# USB-PD.net
KiCad netlist of a schematic drawn in Altium Designer
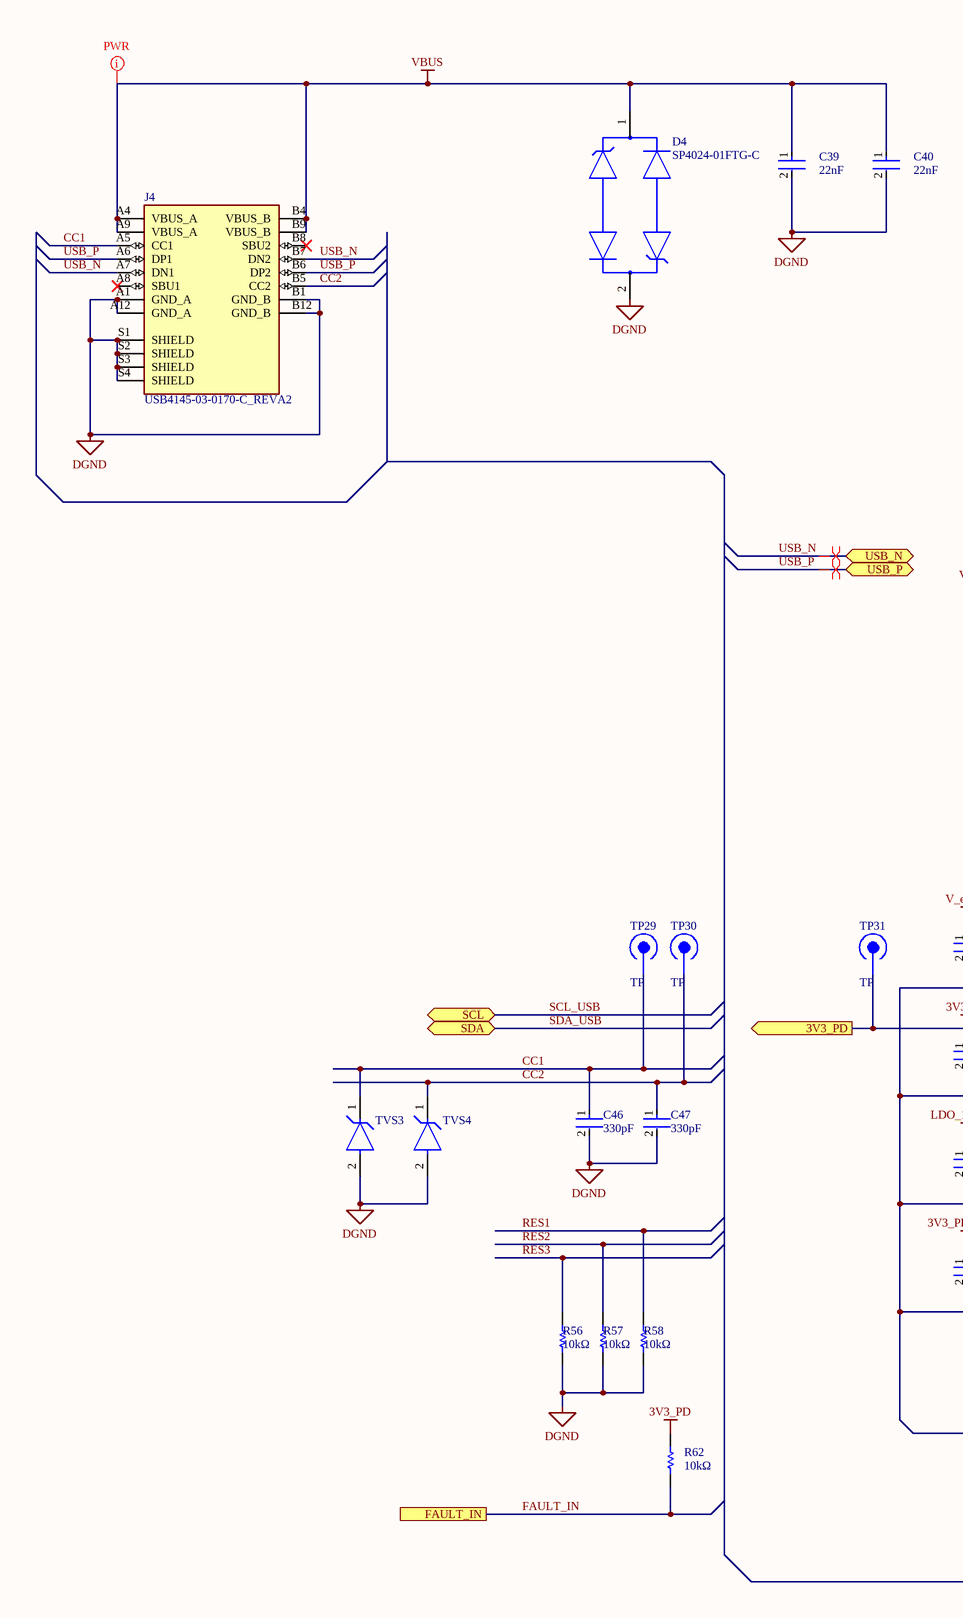
[diagram p0: USB-PD.SchDoc, left]
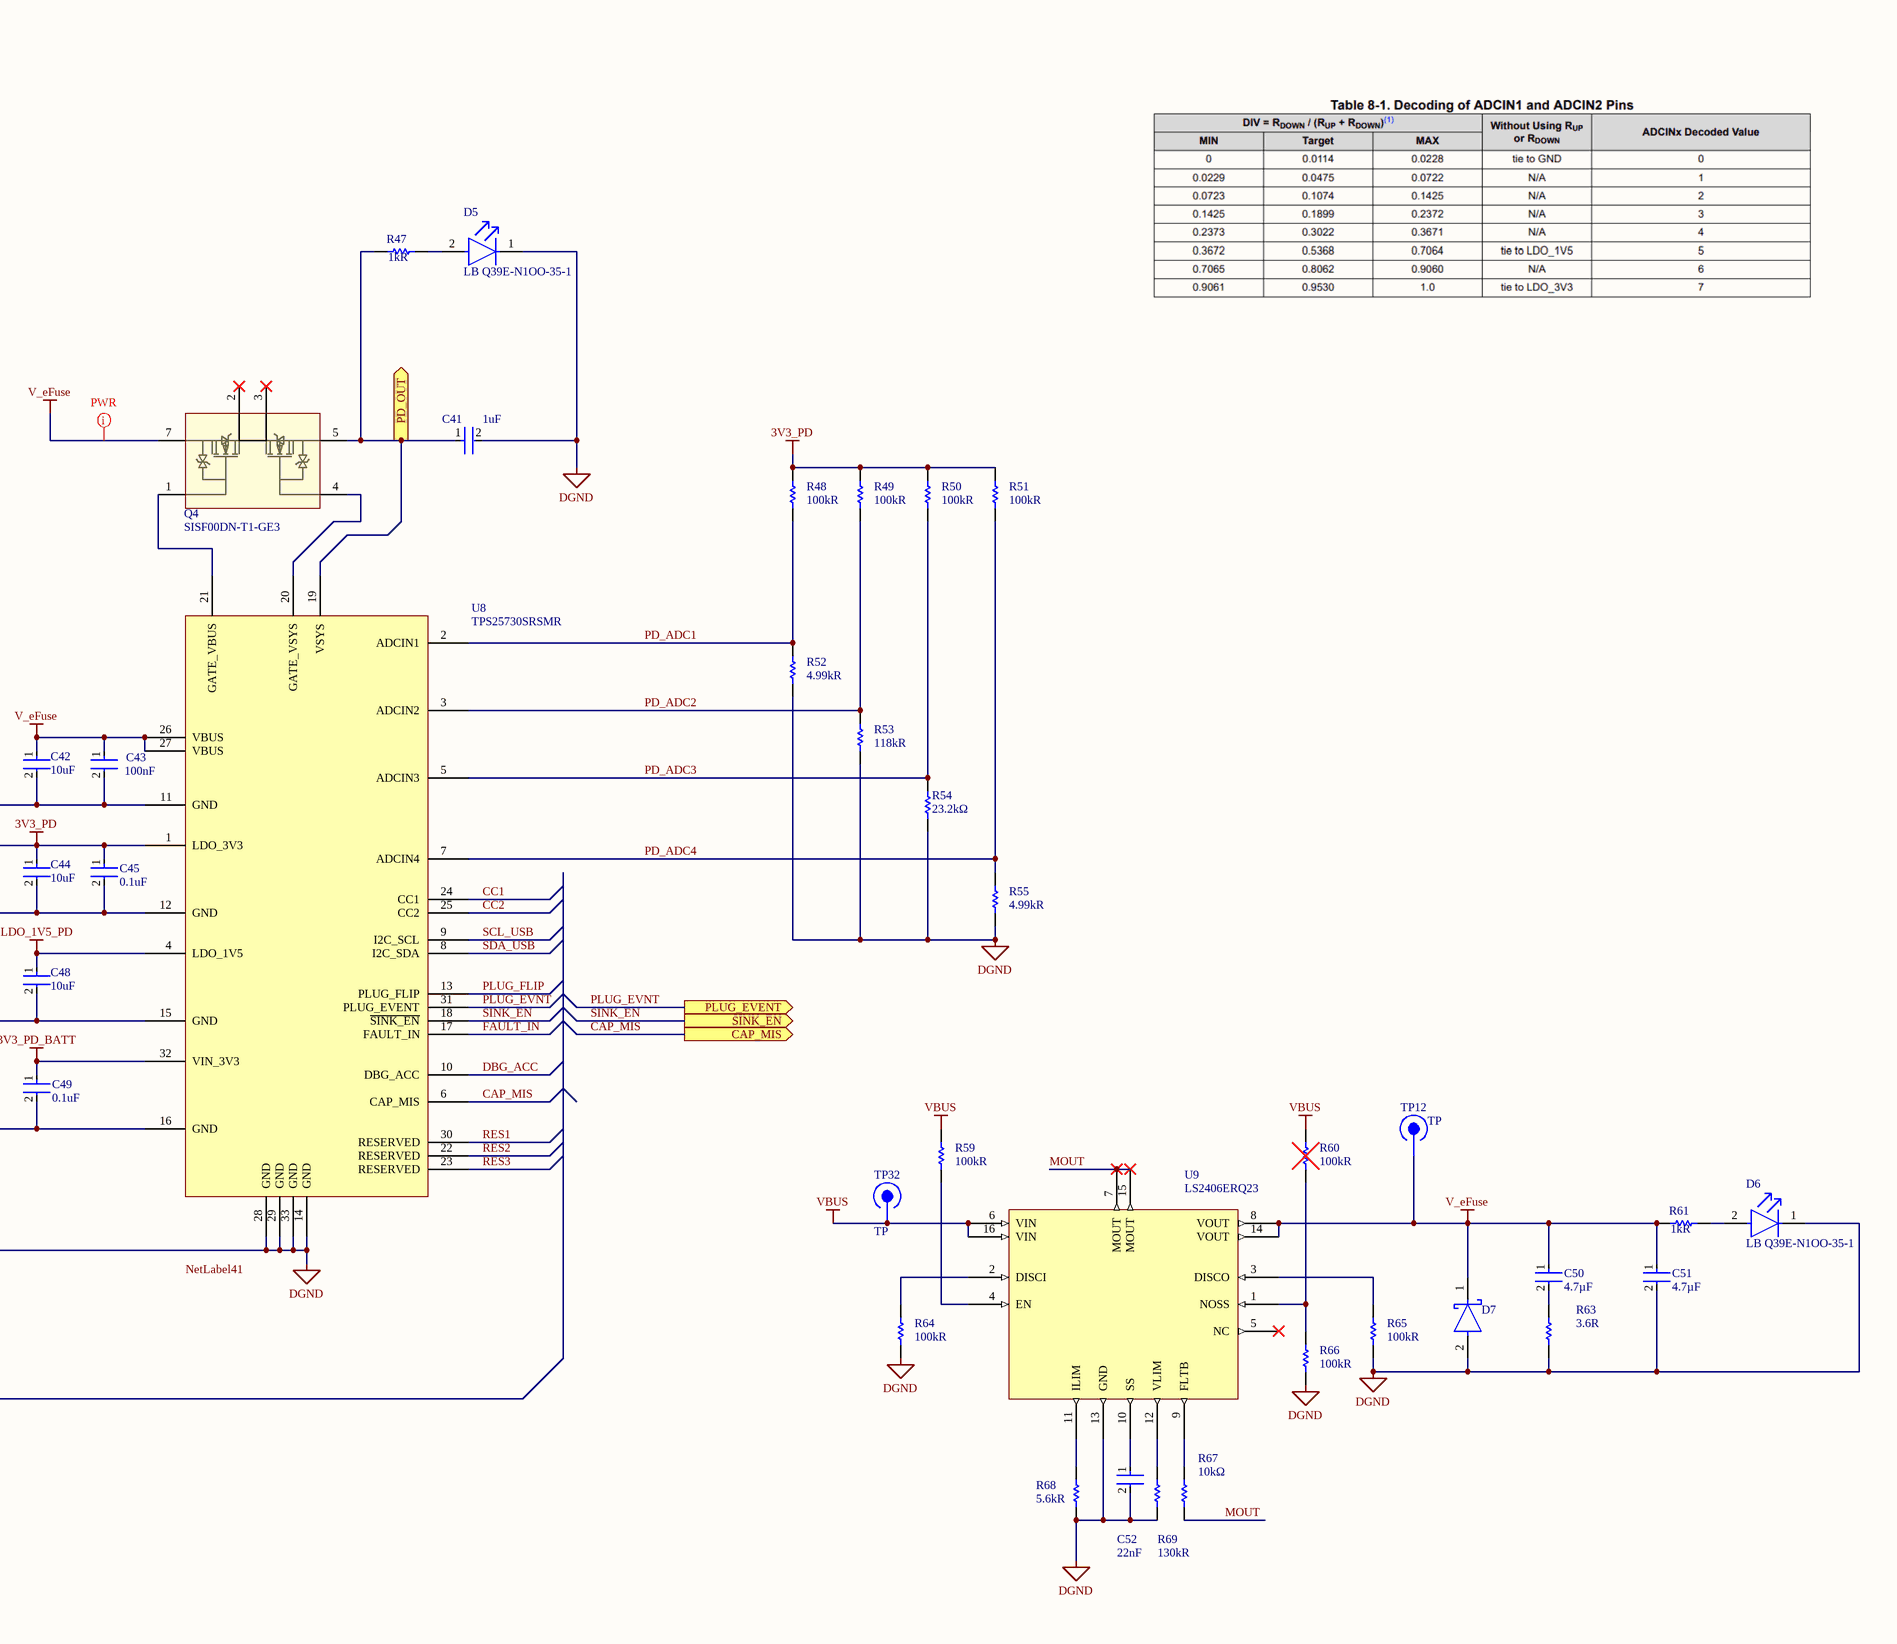
[diagram p1: USB-PD.SchDoc, right]

(export (version "E")
  (design (tool "Eeschema 10.0.6"))
  (components
    (comp (ref "C39")
      (value "22nF")
      (footprint "FP-GRM155-0_05-MFG")
      (fields (field (name "MANUFACTURER") "Murata") (field (name "Comment") "GRM155R71H223KA12D"))
      (libsource (lib "Digital Shovel") (part "02cd4be3c70576c341d710602a673aa"))
    )
    (comp (ref "C40")
      (value "22nF")
      (footprint "FP-GRM155-0_05-MFG")
      (fields (field (name "MANUFACTURER") "Murata") (field (name "Comment") "GRM155R71H223KA12D"))
      (libsource (lib "Digital Shovel") (part "02cd4be3c70576c341d710602a673aa"))
    )
    (comp (ref "C41")
      (value "1uF")
      (footprint "FP-GCM188-0_1-IPC_B")
      (fields (field (name "MANUFACTURER") "Murata") (field (name "Comment") "GCM188R71E105KA64J"))
      (libsource (lib "Digital Shovel") (part "02cd4be3c70576c341d710602a673aa"))
    )
    (comp (ref "C42")
      (value "10uF")
      (footprint "FP-GRM155-0_2-MFG")
      (fields (field (name "Comment") "GRM155R61A106ME11D"))
      (libsource (lib "Digital Shovel") (part "b4654b650e69147ec39a6b967a45e02"))
    )
    (comp (ref "C43")
      (value "100nF")
      (footprint "FP-CC0402-IPC_B")
      (fields (field (name "Comment") "CC0402KRX7R9BB104"))
      (libsource (lib "Digital Shovel") (part "11868f565c42a9108669ba33697ecf6"))
    )
    (comp (ref "C44")
      (value "10uF")
      (footprint "FP-GRM155-0_2-MFG")
      (fields (field (name "Comment") "GRM155R61A106ME11D"))
      (libsource (lib "Digital Shovel") (part "b4654b650e69147ec39a6b967a45e02"))
    )
    (comp (ref "C45")
      (value "0.1uF")
      (footprint "FP-CC0402-IPC_C")
      (description "Multilayer Ceramic Capacitor, 0.1 uF, 25 V, ± 10%, X7R, 0402 [1005 Metric]")
      (fields (field (name "Comment") "CC0402KRX7R7BB104"))
      (libsource (lib "Digital Shovel") (part "11868f565c42a9108669ba33697ecf6"))
    )
    (comp (ref "C46")
      (value "330pF")
      (footprint "FP-C0402-BB-MFG")
      (fields (field (name "MANUFACTURER") "Kemet") (field (name "Comment") "C0402C331K5RACTU"))
      (libsource (lib "Digital Shovel") (part "b4654b650e69147ec39a6b967a45e02"))
    )
    (comp (ref "C47")
      (value "330pF")
      (footprint "FP-C0402-BB-MFG")
      (fields (field (name "MANUFACTURER") "Kemet") (field (name "Comment") "C0402C331K5RACTU"))
      (libsource (lib "Digital Shovel") (part "b4654b650e69147ec39a6b967a45e02"))
    )
    (comp (ref "C48")
      (value "10uF")
      (footprint "FP-GRM155-0_2-MFG")
      (fields (field (name "Comment") "GRM155R61A106ME11D"))
      (libsource (lib "Digital Shovel") (part "b4654b650e69147ec39a6b967a45e02"))
    )
    (comp (ref "C49")
      (value "0.1uF")
      (footprint "FP-CC0402-IPC_C")
      (description "Multilayer Ceramic Capacitor, 0.1 uF, 25 V, ± 10%, X7R, 0402 [1005 Metric]")
      (fields (field (name "Comment") "CC0402KRX7R7BB104"))
      (libsource (lib "Digital Shovel") (part "11868f565c42a9108669ba33697ecf6"))
    )
    (comp (ref "C50")
      (value "4.7µF")
      (footprint "FP-GRM21B-0_15-IPC_A")
      (fields (field (name "Comment") "GRM21BR61H475KE51L"))
      (libsource (lib "Digital Shovel") (part "b4654b650e69147ec39a6b967a45e02"))
    )
    (comp (ref "C51")
      (value "4.7µF")
      (footprint "FP-GRM21B-0_15-IPC_A")
      (fields (field (name "Comment") "GRM21BR61H475KE51L"))
      (libsource (lib "Digital Shovel") (part "b4654b650e69147ec39a6b967a45e02"))
    )
    (comp (ref "C52")
      (value "22nF")
      (footprint "FP-GRM155-0_05-MFG")
      (fields (field (name "MANUFACTURER") "Murata") (field (name "Comment") "GRM155R71H223KA12D"))
      (libsource (lib "Digital Shovel") (part "02cd4be3c70576c341d710602a673aa"))
    )
    (comp (ref "D4")
      (value "SP4024-01FTG-C")
      (footprint "FP-SP4024-CA-MFG")
      (description "Trans Voltage Suppressor Diode, 350W, 24V V(RWM), Bidirectional, 1 Element, Silicon")
      (fields (field (name "MANUFACTURER") "Littelfuse"))
      (libsource (lib "Digital Shovel") (part "83d03e45b50b4a497300f60ade81f7d"))
    )
    (comp (ref "D5")
      (value "LB Q39E-N1OO-35-1")
      (footprint "FP-LB_Q39E-MFG")
      (description "LED BLUE DIFFUSED 0603 SMD")
      (libsource (lib "Altium Content Vault") (part "8706943c75ba83719d021d2fdc84c58"))
    )
    (comp (ref "D6")
      (value "LB Q39E-N1OO-35-1")
      (footprint "FP-LB_Q39E-MFG")
      (description "LED BLUE DIFFUSED 0603 SMD")
      (libsource (lib "Altium Content Vault") (part "8706943c75ba83719d021d2fdc84c58"))
    )
    (comp (ref "D7")
      (value "PMEG4030ER,115")
      (footprint "FP-SOD123W-MFG")
      (description "Rectifier Diode, Schottky, 1 Phase, 1 Element, 3A, 40V V(RRM), Silicon")
      (fields (field (name "MANUFACTURER") "Nexperia"))
      (libsource (lib "Digital Shovel") (part "e9b750318ede8d9850c058872da20e7"))
    )
    (comp (ref "J4")
      (value "USB4145-03-0170-C_REVA2")
      (footprint "GCT_USB4145-03-0170-C_REVA2")
      (libsource (lib "Digital Shovel") (part "USB4145-03-0170-C_REVA2"))
    )
    (comp (ref "Q4")
      (value "SISF00DN-T1-GE3")
      (footprint "New footprint 1")
      (description "Power Field-Effect Transistor")
      (fields (field (name "MANUFACTURER") "Vishay"))
      (libsource (lib "Digital Shovel") (part "New symbol 1"))
    )
    (comp (ref "R47")
      (value "1kR")
      (footprint "FP-ERA2A-MFG")
      (description "Fixed Resistor, Thin Film, 0.063W, 1000ohm, 50V, 0.1% +/-Tol, 25ppm/Cel, Surface Mount, 0402")
      (fields (field (name "MANUFACTURER") "Panasonic") (field (name "Comment") "ERA-2AEB102X"))
      (libsource (lib "Digital Shovel") (part "1029c3af85768c4190bb7ad29bc67b5"))
    )
    (comp (ref "R48")
      (value "100kR")
      (footprint "RESC1005X40X25LL10T10")
      (fields (field (name "Comment") "RK73H1ETTP1003F"))
      (libsource (lib "Digital Shovel") (part "RES"))
    )
    (comp (ref "R49")
      (value "100kR")
      (footprint "RESC1005X40X25LL10T10")
      (fields (field (name "Comment") "RK73H1ETTP1003F"))
      (libsource (lib "Digital Shovel") (part "RES"))
    )
    (comp (ref "R50")
      (value "100kR")
      (footprint "RESC1005X40X25LL10T10")
      (fields (field (name "Comment") "RK73H1ETTP1003F"))
      (libsource (lib "Digital Shovel") (part "RES"))
    )
    (comp (ref "R51")
      (value "100kR")
      (footprint "RESC1005X40X25LL10T10")
      (fields (field (name "Comment") "RK73H1ETTP1003F"))
      (libsource (lib "Digital Shovel") (part "RES"))
    )
    (comp (ref "R52")
      (value "4.99kR")
      (footprint "RESC1005X40X25LL10T10")
      (fields (field (name "Comment") "RK73H1ETTP4991F"))
      (libsource (lib "Digital Shovel") (part "RES"))
    )
    (comp (ref "R53")
      (value "118kR")
      (footprint "RESC1005X40X25LL10T10")
      (fields (field (name "Comment") "RK73H1ETTP1183F"))
      (libsource (lib "Digital Shovel") (part "RES"))
    )
    (comp (ref "R54")
      (value "23.2kΩ")
      (footprint "RESC1005X40X25LL10T10")
      (fields (field (name "Comment") "RK73H1ETTP2322F"))
      (libsource (lib "Digital Shovel") (part "RES"))
    )
    (comp (ref "R55")
      (value "4.99kR")
      (footprint "RESC1005X40X25LL10T10")
      (fields (field (name "Comment") "RK73H1ETTP4991F"))
      (libsource (lib "Digital Shovel") (part "RES"))
    )
    (comp (ref "R56")
      (value "10kΩ")
      (footprint "RESC1005X40X25LL10T10")
      (fields (field (name "Comment") "RK73B1ETTP103J"))
      (libsource (lib "Digital Shovel") (part "RES"))
    )
    (comp (ref "R57")
      (value "10kΩ")
      (footprint "RESC1005X40X25LL10T10")
      (fields (field (name "Comment") "RK73B1ETTP103J"))
      (libsource (lib "Digital Shovel") (part "RES"))
    )
    (comp (ref "R58")
      (value "10kΩ")
      (footprint "RESC1005X40X25LL10T10")
      (fields (field (name "Comment") "RK73B1ETTP103J"))
      (libsource (lib "Digital Shovel") (part "RES"))
    )
    (comp (ref "R59")
      (value "100kR")
      (footprint "RESC1005X40X25LL10T10")
      (fields (field (name "Comment") "RK73H1ETTP1003F"))
      (libsource (lib "Digital Shovel") (part "RES"))
    )
    (comp (ref "R60")
      (value "100kR")
      (footprint "RESC1005X40X25LL10T10")
      (fields (field (name "Comment") "RK73H1ETTP1003F"))
      (libsource (lib "Digital Shovel") (part "RES"))
    )
    (comp (ref "R61")
      (value "1kR")
      (footprint "FP-ERA2A-MFG")
      (description "Fixed Resistor, Thin Film, 0.063W, 1000ohm, 50V, 0.1% +/-Tol, 25ppm/Cel, Surface Mount, 0402")
      (fields (field (name "MANUFACTURER") "Panasonic") (field (name "Comment") "ERA-2AEB102X"))
      (libsource (lib "Digital Shovel") (part "1029c3af85768c4190bb7ad29bc67b5"))
    )
    (comp (ref "R62")
      (value "10kΩ")
      (footprint "RESC1005X40X25LL10T10")
      (fields (field (name "Comment") "RK73B1ETTP103J"))
      (libsource (lib "Digital Shovel") (part "RES"))
    )
    (comp (ref "R63")
      (value "3.6R")
      (footprint "FP-RK73H2A-MFG")
      (fields (field (name "Comment") "RK73H2ATTD3R60F"))
      (libsource (lib "Digital Shovel") (part "1029c3af85768c4190bb7ad29bc67b5"))
    )
    (comp (ref "R64")
      (value "100kR")
      (footprint "RESC1005X40X25LL10T10")
      (fields (field (name "Comment") "RK73H1ETTP1003F"))
      (libsource (lib "Digital Shovel") (part "RES"))
    )
    (comp (ref "R65")
      (value "100kR")
      (footprint "RESC1005X40X25LL10T10")
      (fields (field (name "Comment") "RK73H1ETTP1003F"))
      (libsource (lib "Digital Shovel") (part "RES"))
    )
    (comp (ref "R66")
      (value "100kR")
      (footprint "RESC1005X40X25LL10T10")
      (fields (field (name "Comment") "RK73H1ETTP1003F"))
      (libsource (lib "Digital Shovel") (part "RES"))
    )
    (comp (ref "R67")
      (value "10kΩ")
      (footprint "RESC1005X40X25LL10T10")
      (fields (field (name "Comment") "RK73B1ETTP103J"))
      (libsource (lib "Digital Shovel") (part "RES"))
    )
    (comp (ref "R68")
      (value "5.6kR")
      (footprint "RESC1005X40X25LL10T10")
      (fields (field (name "Comment") "RK73H1ETTP5601F"))
      (libsource (lib "Digital Shovel") (part "RES"))
    )
    (comp (ref "R69")
      (value "130kR")
      (footprint "RESC1005X40X25NL10T10")
      (fields (field (name "PART NUMBER") "RK73H1ETTP1303F") (field (name "MANUFACTURER") "KOA Speer"))
      (libsource (lib "Altium Content Vault") (part "RES"))
    )
    (comp (ref "TP12")
      (value "TP")
      (footprint "TP-Footprint-1")
      (description "digital shovel test point")
      (libsource (lib "Digital Shovel") (part "TP-Symbol-1"))
    )
    (comp (ref "TP29")
      (value "TP")
      (footprint "TP-Footprint-1")
      (description "digital shovel test point")
      (libsource (lib "Digital Shovel") (part "TP-Symbol-1"))
    )
    (comp (ref "TP30")
      (value "TP")
      (footprint "TP-Footprint-1")
      (description "digital shovel test point")
      (libsource (lib "Digital Shovel") (part "TP-Symbol-1"))
    )
    (comp (ref "TP31")
      (value "TP")
      (footprint "TP-Footprint-1")
      (description "digital shovel test point")
      (libsource (lib "Digital Shovel") (part "TP-Symbol-1"))
    )
    (comp (ref "TP32")
      (value "TP")
      (footprint "TP-Footprint-1")
      (description "digital shovel test point")
      (libsource (lib "Digital Shovel") (part "TP-Symbol-1"))
    )
    (comp (ref "TVS3")
      (value "PESD5Z5.0,115")
      (footprint "DIO_BAS716,115")
      (description "Trans Voltage Suppressor Diode, 180W, 5V V(RWM), Unidirectional, 1 Element, Silicon")
      (fields (field (name "MANUFACTURER") "Nexperia"))
      (libsource (lib "Digital Shovel") (part "PESD5Z5.0,115-Symbol-1"))
    )
    (comp (ref "TVS4")
      (value "PESD5Z5.0,115")
      (footprint "DIO_BAS716,115")
      (description "Trans Voltage Suppressor Diode, 180W, 5V V(RWM), Unidirectional, 1 Element, Silicon")
      (fields (field (name "MANUFACTURER") "Nexperia"))
      (libsource (lib "Digital Shovel") (part "PESD5Z5.0,115-Symbol-1"))
    )
    (comp (ref "U8")
      (value "TPS25730SRSMR")
      (footprint "QFN40P400X400X100_HS-33N")
      (fields (field (name "MANUFACTURER") "Texas Instruments"))
      (libsource (lib "Digital Shovel") (part "TPS25730SRSMR-Symbol-1"))
    )
    (comp (ref "U9")
      (value "LS2406ERQ23")
      (footprint "LS2406ERQ23-Footprint-1")
      (description "28V/6A Efuse With True Rcb & Frs")
      (fields (field (name "MANUFACTURER") "Littelfuse"))
      (libsource (lib "Digital Shovel") (part "LS2406ERQ23-Symbol-1"))
    )
  )
  (nets
    (net (code "1") (name "/CAP_MIS") (class "Default")
      (node (ref "U8") (pin "6") (pinfunction "CAP_MIS_6") (pintype "passive"))
    )
    (net (code "2") (name "/CC1") (class "Default")
      (node (ref "C46") (pin "1") (pinfunction "1_1") (pintype "passive"))
      (node (ref "J4") (pin "A5") (pinfunction "CC1_A5") (pintype "bidirectional"))
      (node (ref "TP29") (pin "1") (pintype "passive"))
      (node (ref "TVS3") (pin "1") (pinfunction "1_1") (pintype "passive"))
      (node (ref "U8") (pin "24") (pinfunction "CC1_24") (pintype "passive"))
    )
    (net (code "3") (name "/CC2") (class "Default")
      (node (ref "C47") (pin "1") (pinfunction "1_1") (pintype "passive"))
      (node (ref "J4") (pin "B5") (pinfunction "CC2_B5") (pintype "bidirectional"))
      (node (ref "TP30") (pin "1") (pintype "passive"))
      (node (ref "TVS4") (pin "1") (pinfunction "1_1") (pintype "passive"))
      (node (ref "U8") (pin "25") (pinfunction "CC2_25") (pintype "passive"))
    )
    (net (code "4") (name "/DBG_ACC") (class "Default")
      (node (ref "U8") (pin "10") (pinfunction "DBG_ACC_10") (pintype "passive"))
    )
    (net (code "5") (name "/FAULT_IN") (class "Default")
      (node (ref "R62") (pin "1") (pinfunction "1_1") (pintype "passive"))
      (node (ref "U8") (pin "17") (pinfunction "FAULT_IN_17") (pintype "passive"))
    )
    (net (code "6") (name "/MOUT") (class "Default")
      (node (ref "R67") (pin "1") (pinfunction "1_1") (pintype "passive"))
      (node (ref "U9") (pin "15") (pinfunction "MOUT_15") (pintype "output"))
      (node (ref "U9") (pin "7") (pinfunction "MOUT_7") (pintype "output"))
    )
    (net (code "8") (name "/PD_ADC1") (class "Default")
      (node (ref "R48") (pin "1") (pinfunction "1_1") (pintype "passive"))
      (node (ref "R52") (pin "2") (pinfunction "2_2") (pintype "passive"))
      (node (ref "U8") (pin "2") (pinfunction "ADCIN1_2") (pintype "passive"))
    )
    (net (code "9") (name "/PD_ADC2") (class "Default")
      (node (ref "R49") (pin "1") (pinfunction "1_1") (pintype "passive"))
      (node (ref "R53") (pin "2") (pinfunction "2_2") (pintype "passive"))
      (node (ref "U8") (pin "3") (pinfunction "ADCIN2_3") (pintype "passive"))
    )
    (net (code "10") (name "/PD_ADC3") (class "Default")
      (node (ref "R50") (pin "1") (pinfunction "1_1") (pintype "passive"))
      (node (ref "R54") (pin "2") (pinfunction "2_2") (pintype "passive"))
      (node (ref "U8") (pin "5") (pinfunction "ADCIN3_5") (pintype "passive"))
    )
    (net (code "11") (name "/PD_ADC4") (class "Default")
      (node (ref "R51") (pin "1") (pinfunction "1_1") (pintype "passive"))
      (node (ref "R55") (pin "2") (pinfunction "2_2") (pintype "passive"))
      (node (ref "U8") (pin "7") (pinfunction "ADCIN4_7") (pintype "passive"))
    )
    (net (code "12") (name "/PD_OUT") (class "Default")
      (node (ref "C41") (pin "1") (pinfunction "1_1") (pintype "passive"))
      (node (ref "Q4") (pin "5") (pinfunction "S2_5") (pintype "passive"))
      (node (ref "R47") (pin "2") (pinfunction "2_2") (pintype "passive"))
      (node (ref "U8") (pin "19") (pinfunction "VSYS_19") (pintype "passive"))
    )
    (net (code "13") (name "/PLUG_EVNT") (class "Default")
      (node (ref "U8") (pin "31") (pinfunction "PLUG_EVENT_31") (pintype "passive"))
    )
    (net (code "14") (name "/PLUG_FLIP") (class "Default")
      (node (ref "U8") (pin "13") (pinfunction "PLUG_FLIP_13") (pintype "passive"))
    )
    (net (code "15") (name "/RES1") (class "Default")
      (node (ref "R58") (pin "2") (pinfunction "2_2") (pintype "passive"))
      (node (ref "U8") (pin "30") (pinfunction "RESERVED_30") (pintype "passive"))
    )
    (net (code "16") (name "/RES2") (class "Default")
      (node (ref "R57") (pin "2") (pinfunction "2_2") (pintype "passive"))
      (node (ref "U8") (pin "22") (pinfunction "RESERVED_22") (pintype "passive"))
    )
    (net (code "17") (name "/RES3") (class "Default")
      (node (ref "R56") (pin "2") (pinfunction "2_2") (pintype "passive"))
      (node (ref "U8") (pin "23") (pinfunction "RESERVED_23") (pintype "passive"))
    )
    (net (code "18") (name "/SCL_USB") (class "Default")
      (node (ref "U8") (pin "9") (pinfunction "I2C_SCL_9") (pintype "passive"))
    )
    (net (code "19") (name "/SDA_USB") (class "Default")
      (node (ref "U8") (pin "8") (pinfunction "I2C_SDA_8") (pintype "passive"))
    )
    (net (code "20") (name "/SINK_EN") (class "Default")
      (node (ref "U8") (pin "18") (pinfunction "~{SINK_EN}_18") (pintype "passive"))
    )
    (net (code "21") (name "/USB_N") (class "Default")
      (node (ref "J4") (pin "A7") (pinfunction "DN1_A7") (pintype "bidirectional"))
      (node (ref "J4") (pin "B7") (pinfunction "DN2_B7") (pintype "bidirectional"))
    )
    (net (code "22") (name "/USB_P") (class "Default")
      (node (ref "J4") (pin "A6") (pinfunction "DP1_A6") (pintype "bidirectional"))
      (node (ref "J4") (pin "B6") (pinfunction "DP2_B6") (pintype "bidirectional"))
    )
    (net (code "23") (name "3V3_PD") (class "Default")
      (node (ref "C44") (pin "1") (pinfunction "1_1") (pintype "passive"))
      (node (ref "C45") (pin "1") (pinfunction "1_1") (pintype "passive"))
      (node (ref "R48") (pin "2") (pinfunction "2_2") (pintype "passive"))
      (node (ref "R49") (pin "2") (pinfunction "2_2") (pintype "passive"))
      (node (ref "R50") (pin "2") (pinfunction "2_2") (pintype "passive"))
      (node (ref "R51") (pin "2") (pinfunction "2_2") (pintype "passive"))
      (node (ref "R62") (pin "2") (pinfunction "2_2") (pintype "passive"))
      (node (ref "TP31") (pin "1") (pintype "passive"))
      (node (ref "U8") (pin "1") (pinfunction "LDO_3V3_1") (pintype "passive"))
    )
    (net (code "24") (name "3V3_PD_BATT") (class "Default")
      (node (ref "C49") (pin "1") (pinfunction "1_1") (pintype "passive"))
      (node (ref "U8") (pin "32") (pinfunction "VIN_3V3_32") (pintype "passive"))
    )
    (net (code "25") (name "DGND") (class "Default")
      (node (ref "C39") (pin "2") (pinfunction "2_2") (pintype "passive"))
      (node (ref "C40") (pin "2") (pinfunction "2_2") (pintype "passive"))
      (node (ref "C41") (pin "2") (pinfunction "2_2") (pintype "passive"))
      (node (ref "C42") (pin "2") (pinfunction "2_2") (pintype "passive"))
      (node (ref "C43") (pin "2") (pinfunction "2_2") (pintype "passive"))
      (node (ref "C44") (pin "2") (pinfunction "2_2") (pintype "passive"))
      (node (ref "C45") (pin "2") (pinfunction "2_2") (pintype "passive"))
      (node (ref "C46") (pin "2") (pinfunction "2_2") (pintype "passive"))
      (node (ref "C47") (pin "2") (pinfunction "2_2") (pintype "passive"))
      (node (ref "C48") (pin "2") (pinfunction "2_2") (pintype "passive"))
      (node (ref "C49") (pin "2") (pinfunction "2_2") (pintype "passive"))
      (node (ref "C51") (pin "2") (pinfunction "2_2") (pintype "passive"))
      (node (ref "C52") (pin "2") (pinfunction "2_2") (pintype "passive"))
      (node (ref "D4") (pin "2") (pinfunction "2_2") (pintype "passive"))
      (node (ref "D5") (pin "1") (pinfunction "C_1") (pintype "passive"))
      (node (ref "D6") (pin "1") (pinfunction "C_1") (pintype "passive"))
      (node (ref "D7") (pin "2") (pinfunction "A_2") (pintype "passive"))
      (node (ref "J4") (pin "A1") (pinfunction "GND_A_A1") (pintype "power_in"))
      (node (ref "J4") (pin "A12") (pinfunction "GND_A_A12") (pintype "power_in"))
      (node (ref "J4") (pin "B1") (pinfunction "GND_B_B1") (pintype "power_in"))
      (node (ref "J4") (pin "B12") (pinfunction "GND_B_B12") (pintype "power_in"))
      (node (ref "J4") (pin "S1") (pinfunction "SHIELD_S1") (pintype "passive"))
      (node (ref "J4") (pin "S2") (pinfunction "SHIELD_S2") (pintype "passive"))
      (node (ref "J4") (pin "S3") (pinfunction "SHIELD_S3") (pintype "passive"))
      (node (ref "J4") (pin "S4") (pinfunction "SHIELD_S4") (pintype "passive"))
      (node (ref "R52") (pin "1") (pinfunction "1_1") (pintype "passive"))
      (node (ref "R53") (pin "1") (pinfunction "1_1") (pintype "passive"))
      (node (ref "R54") (pin "1") (pinfunction "1_1") (pintype "passive"))
      (node (ref "R55") (pin "1") (pinfunction "1_1") (pintype "passive"))
      (node (ref "R56") (pin "1") (pinfunction "1_1") (pintype "passive"))
      (node (ref "R57") (pin "1") (pinfunction "1_1") (pintype "passive"))
      (node (ref "R58") (pin "1") (pinfunction "1_1") (pintype "passive"))
      (node (ref "R63") (pin "1") (pinfunction "1_1") (pintype "passive"))
      (node (ref "R64") (pin "1") (pinfunction "1_1") (pintype "passive"))
      (node (ref "R65") (pin "1") (pinfunction "1_1") (pintype "passive"))
      (node (ref "R66") (pin "1") (pinfunction "1_1") (pintype "passive"))
      (node (ref "R68") (pin "1") (pinfunction "1_1") (pintype "passive"))
      (node (ref "R69") (pin "1") (pinfunction "1_1") (pintype "passive"))
      (node (ref "TVS3") (pin "2") (pinfunction "1_2") (pintype "passive"))
      (node (ref "TVS4") (pin "2") (pinfunction "1_2") (pintype "passive"))
      (node (ref "U8") (pin "11") (pinfunction "GND_11") (pintype "passive"))
      (node (ref "U8") (pin "12") (pinfunction "GND_12") (pintype "passive"))
      (node (ref "U8") (pin "14") (pinfunction "GND_14") (pintype "passive"))
      (node (ref "U8") (pin "15") (pinfunction "GND_15") (pintype "passive"))
      (node (ref "U8") (pin "16") (pinfunction "GND_16") (pintype "passive"))
      (node (ref "U8") (pin "28") (pinfunction "GND_28") (pintype "passive"))
      (node (ref "U8") (pin "29") (pinfunction "GND_29") (pintype "passive"))
      (node (ref "U8") (pin "33") (pinfunction "GND_33") (pintype "passive"))
      (node (ref "U9") (pin "13") (pinfunction "GND_13") (pintype "output"))
    )
    (net (code "26") (name "LDO_1V5_PD") (class "Default")
      (node (ref "C48") (pin "1") (pinfunction "1_1") (pintype "passive"))
      (node (ref "U8") (pin "4") (pinfunction "LDO_1V5_4") (pintype "passive"))
    )
    (net (code "27") (name "Net-(C50-Pad2)") (class "Default")
      (node (ref "C50") (pin "2") (pinfunction "2_2") (pintype "passive"))
      (node (ref "R63") (pin "2") (pinfunction "2_2") (pintype "passive"))
    )
    (net (code "28") (name "Net-(D5-A)") (class "Default")
      (node (ref "D5") (pin "2") (pinfunction "A_2") (pintype "passive"))
      (node (ref "R47") (pin "1") (pinfunction "1_1") (pintype "passive"))
    )
    (net (code "29") (name "Net-(D6-A)") (class "Default")
      (node (ref "D6") (pin "2") (pinfunction "A_2") (pintype "passive"))
      (node (ref "R61") (pin "1") (pinfunction "1_1") (pintype "passive"))
    )
    (net (code "30") (name "Net-(Q4-G1)") (class "Default")
      (node (ref "Q4") (pin "1") (pinfunction "G1_1") (pintype "passive"))
      (node (ref "U8") (pin "21") (pinfunction "GATE_VBUS_21") (pintype "passive"))
    )
    (net (code "31") (name "Net-(Q4-G2)") (class "Default")
      (node (ref "Q4") (pin "4") (pinfunction "G2_4") (pintype "passive"))
      (node (ref "U8") (pin "20") (pinfunction "GATE_VSYS_20") (pintype "passive"))
    )
    (net (code "32") (name "Net-(U9-DISCI)") (class "Default")
      (node (ref "R64") (pin "2") (pinfunction "2_2") (pintype "passive"))
      (node (ref "U9") (pin "2") (pinfunction "DISCI_2") (pintype "input"))
    )
    (net (code "33") (name "Net-(U9-DISCO)") (class "Default")
      (node (ref "R65") (pin "2") (pinfunction "2_2") (pintype "passive"))
      (node (ref "U9") (pin "3") (pinfunction "DISCO_3") (pintype "input"))
    )
    (net (code "34") (name "Net-(U9-EN)") (class "Default")
      (node (ref "R59") (pin "1") (pinfunction "1_1") (pintype "passive"))
      (node (ref "U9") (pin "4") (pinfunction "EN_4") (pintype "input"))
    )
    (net (code "35") (name "Net-(U9-FLTB)") (class "Default")
      (node (ref "R67") (pin "2") (pinfunction "2_2") (pintype "passive"))
      (node (ref "U9") (pin "9") (pinfunction "FLTB_9") (pintype "output"))
    )
    (net (code "36") (name "Net-(U9-ILIM)") (class "Default")
      (node (ref "R68") (pin "2") (pinfunction "2_2") (pintype "passive"))
      (node (ref "U9") (pin "11") (pinfunction "ILIM_11") (pintype "output"))
    )
    (net (code "37") (name "Net-(U9-NOSS)") (class "Default")
      (node (ref "R60") (pin "1") (pinfunction "1_1") (pintype "passive"))
      (node (ref "R66") (pin "2") (pinfunction "2_2") (pintype "passive"))
      (node (ref "U9") (pin "1") (pinfunction "NOSS_1") (pintype "input"))
    )
    (net (code "38") (name "Net-(U9-SS)") (class "Default")
      (node (ref "C52") (pin "1") (pinfunction "1_1") (pintype "passive"))
      (node (ref "U9") (pin "10") (pinfunction "SS_10") (pintype "output"))
    )
    (net (code "39") (name "Net-(U9-VLIM)") (class "Default")
      (node (ref "R69") (pin "2") (pinfunction "2_2") (pintype "passive"))
      (node (ref "U9") (pin "12") (pinfunction "VLIM_12") (pintype "output"))
    )
    (net (code "40") (name "VBUS") (class "Default")
      (node (ref "C39") (pin "1") (pinfunction "1_1") (pintype "passive"))
      (node (ref "C40") (pin "1") (pinfunction "1_1") (pintype "passive"))
      (node (ref "D4") (pin "1") (pinfunction "1_1") (pintype "passive"))
      (node (ref "J4") (pin "A4") (pinfunction "VBUS_A_A4") (pintype "power_in"))
      (node (ref "J4") (pin "A9") (pinfunction "VBUS_A_A9") (pintype "power_in"))
      (node (ref "J4") (pin "B4") (pinfunction "VBUS_B_B4") (pintype "power_in"))
      (node (ref "J4") (pin "B9") (pinfunction "VBUS_B_B9") (pintype "power_in"))
      (node (ref "R59") (pin "2") (pinfunction "2_2") (pintype "passive"))
      (node (ref "R60") (pin "2") (pinfunction "2_2") (pintype "passive"))
      (node (ref "TP32") (pin "1") (pintype "passive"))
      (node (ref "U9") (pin "16") (pinfunction "VIN_16") (pintype "input"))
      (node (ref "U9") (pin "6") (pinfunction "VIN_6") (pintype "input"))
    )
    (net (code "41") (name "V_eFuse") (class "Default")
      (node (ref "C42") (pin "1") (pinfunction "1_1") (pintype "passive"))
      (node (ref "C43") (pin "1") (pinfunction "1_1") (pintype "passive"))
      (node (ref "C50") (pin "1") (pinfunction "1_1") (pintype "passive"))
      (node (ref "C51") (pin "1") (pinfunction "1_1") (pintype "passive"))
      (node (ref "D7") (pin "1") (pinfunction "C_1") (pintype "passive"))
      (node (ref "Q4") (pin "7") (pinfunction "S1_7") (pintype "passive"))
      (node (ref "R61") (pin "2") (pinfunction "2_2") (pintype "passive"))
      (node (ref "TP12") (pin "1") (pintype "passive"))
      (node (ref "U8") (pin "26") (pinfunction "VBUS_26") (pintype "passive"))
      (node (ref "U8") (pin "27") (pinfunction "VBUS_27") (pintype "passive"))
      (node (ref "U9") (pin "14") (pinfunction "VOUT_14") (pintype "output"))
      (node (ref "U9") (pin "8") (pinfunction "VOUT_8") (pintype "output"))
    )
    (net (code "42") (name "unconnected-(J4-SBU1-PadA8)") (class "Default")
      (node (ref "J4") (pin "A8") (pinfunction "SBU1_A8") (pintype "bidirectional+no_connect"))
    )
    (net (code "43") (name "unconnected-(J4-SBU2-PadB8)") (class "Default")
      (node (ref "J4") (pin "B8") (pinfunction "SBU2_B8") (pintype "bidirectional+no_connect"))
    )
    (net (code "44") (name "unconnected-(Q4-S1-Pad2)") (class "Default")
      (node (ref "Q4") (pin "2") (pinfunction "S1_2") (pintype "passive+no_connect"))
    )
    (net (code "45") (name "unconnected-(Q4-S1-Pad3)") (class "Default")
      (node (ref "Q4") (pin "3") (pinfunction "S1_3") (pintype "passive+no_connect"))
    )
    (net (code "46") (name "unconnected-(U9-NC-Pad5)") (class "Default")
      (node (ref "U9") (pin "5") (pinfunction "NC_5") (pintype "output+no_connect"))
    )
  )
)
